# Schematic_1_v73.net
KiCad netlist of a schematic drawn in EAGLE
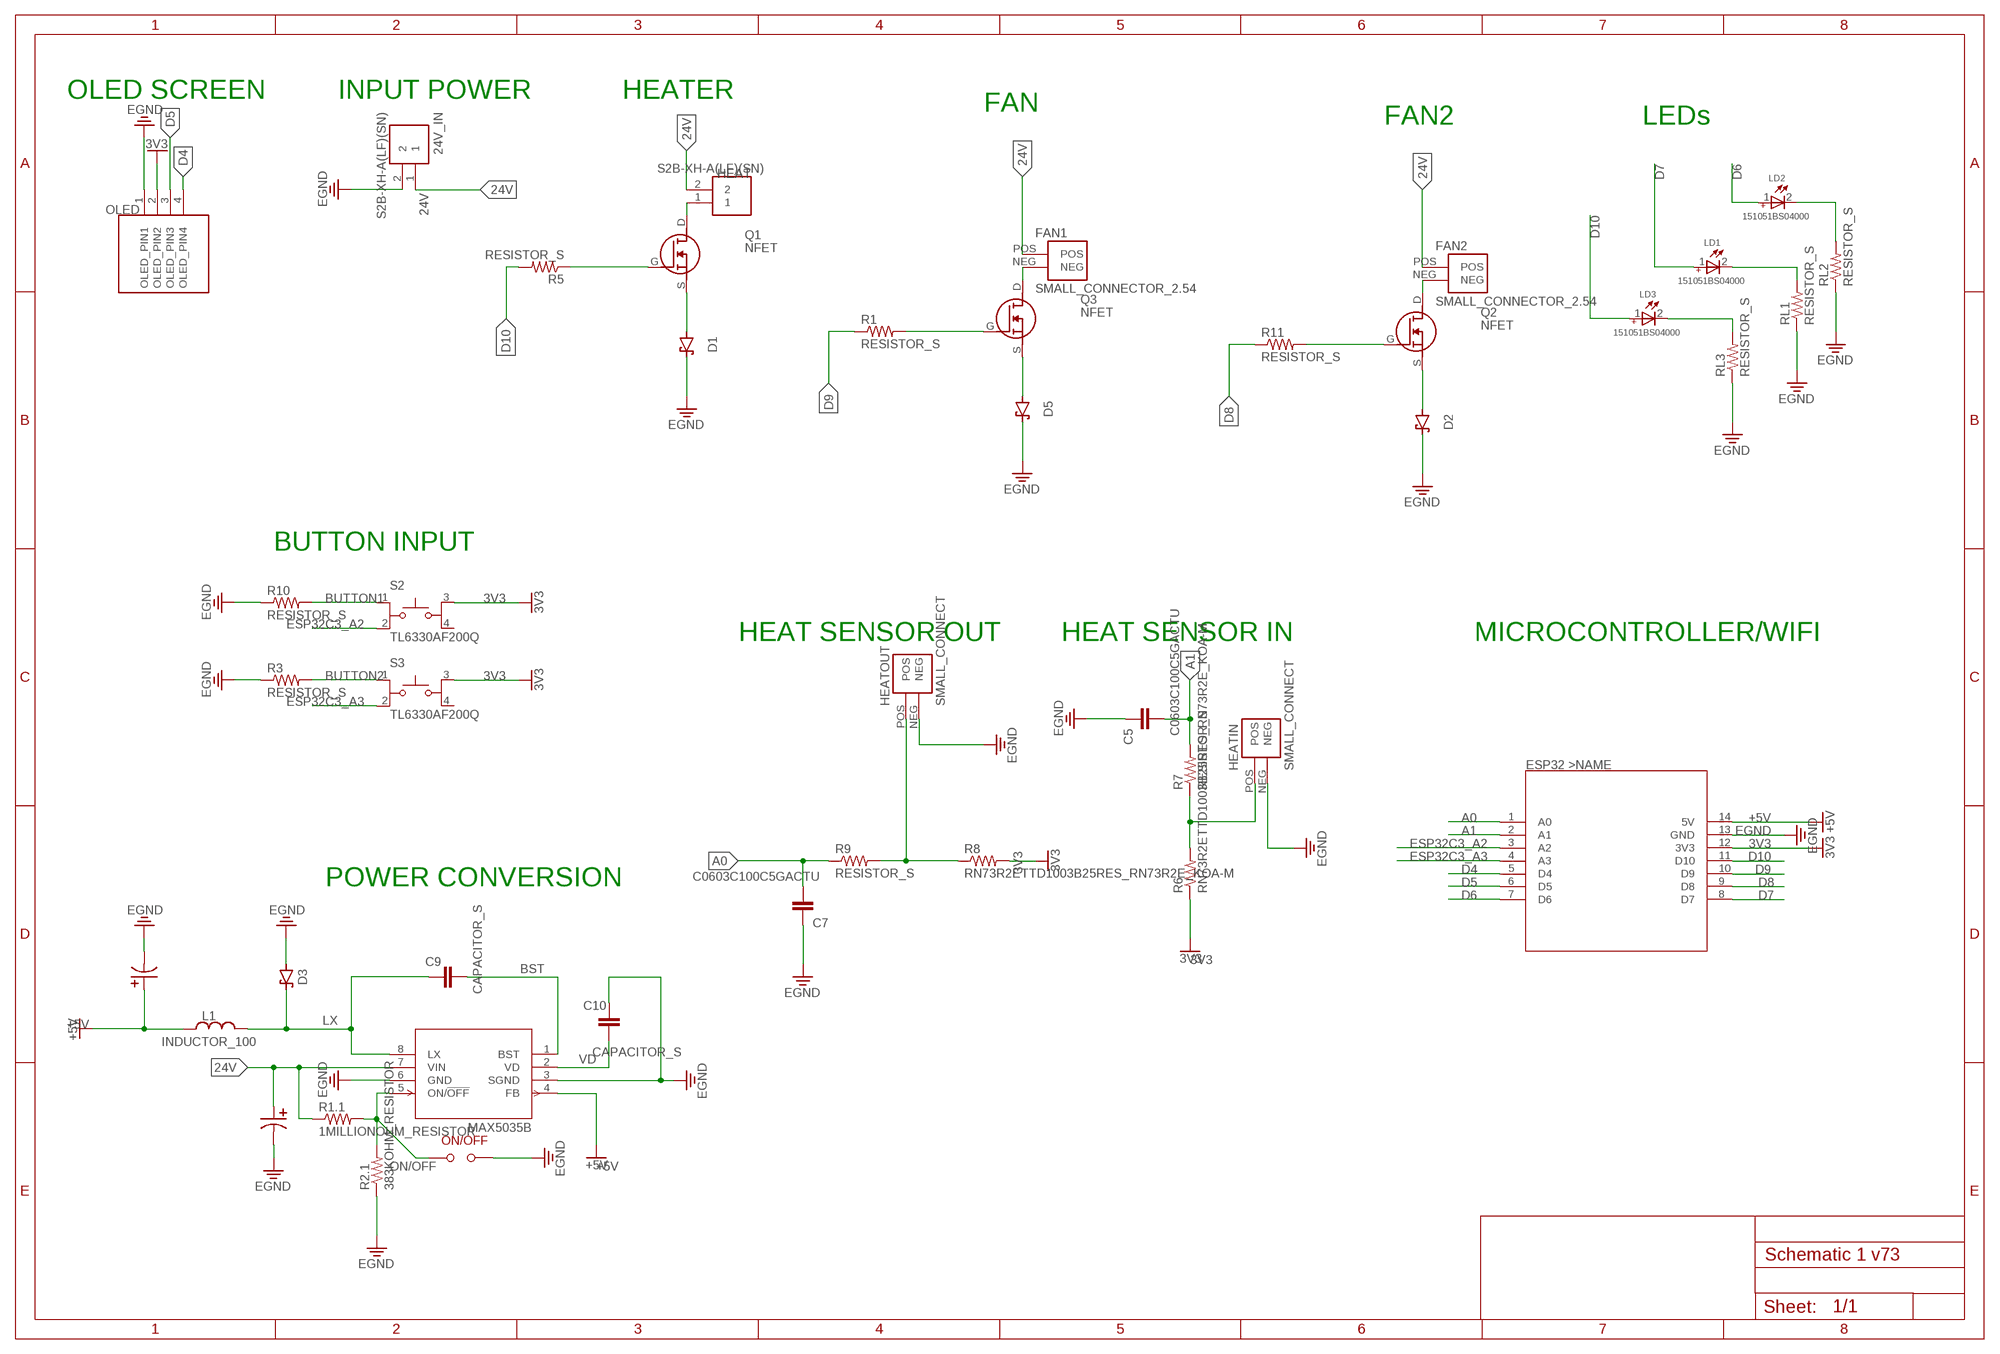
[diagram p0: schematic, sheet 1]

(export (version "E")
  (design (tool "Eeschema 10.0.6"))
  (components
    (comp (ref "24V_IN")
      (value "S2B-XH-A(LF)(SN)")
      (footprint "eagle-import:HDR-02_RA")
      (fields
        (field (name "DIGIKEY_PART_NUMBER") "455-2257-ND")
        (field (name "MANUFACTURER") "JST Sales America Inc.")
        (field (name "CREATED_BY") "PCBLayout.com")
      )
      (libsource (lib "eagle-import") (part "S2B-XH-A(LF)(SN)"))
    )
    (comp (ref "C5")
      (value "C0603C100C5GACTU")
      (footprint "eagle-import:CAP_0603")
      (fields
        (field (name "DIGIKEY_PART_NUMBER") "399-7814-2-ND")
        (field (name "MANUFACTURER") "KEMET")
        (field (name "CREATED_BY") "PCBLayout.com")
      )
      (libsource (lib "eagle-import") (part "C0603C100C5GACTU"))
    )
    (comp (ref "C7")
      (value "C0603C100C5GACTU")
      (footprint "eagle-import:CAP_0603")
      (fields
        (field (name "DIGIKEY_PART_NUMBER") "399-7814-2-ND")
        (field (name "MANUFACTURER") "KEMET")
        (field (name "CREATED_BY") "PCBLayout.com")
      )
      (libsource (lib "eagle-import") (part "C0603C100C5GACTU"))
    )
    (comp (ref "C9")
      (value "CAPACITOR_S")
      (footprint "eagle-import:CAPACITOR_M")
      (libsource (lib "eagle-import") (part "CAPACITOR_M"))
    )
    (comp (ref "C10")
      (value "CAPACITOR_S")
      (footprint "eagle-import:CAPACITOR_M")
      (libsource (lib "eagle-import") (part "CAPACITOR_M"))
    )
    (comp (ref "D1")
      (value "ES1D")
      (footprint "eagle-import:SCHOTTKY_DIODE_S")
      (libsource (lib "eagle-import") (part "SCHOTTKY_S"))
    )
    (comp (ref "D2")
      (value "ES1D")
      (footprint "eagle-import:SCHOTTKY_DIODE_S")
      (libsource (lib "eagle-import") (part "SCHOTTKY_S"))
    )
    (comp (ref "D3")
      (value "MBR0520LT1G")
      (footprint "eagle-import:PANJIT_SB52AFC~SB56AFC_SERIES_DIODE")
      (libsource (lib "eagle-import") (part "PANJIT_SB52AFC~SB56AFC_SERIES_DIODE_SCHOTTKY"))
    )
    (comp (ref "D5")
      (value "ES1D")
      (footprint "eagle-import:SCHOTTKY_DIODE_S")
      (libsource (lib "eagle-import") (part "SCHOTTKY_S"))
    )
    (comp (ref "ESP32C3")
      (value "XIAO_ESP32C3_ALT")
      (footprint "eagle-import:XIIO_ESP32C3_ALT")
      (libsource (lib "eagle-import") (part "XIAO_ESP32C3_ALT"))
    )
    (comp (ref "FAN1")
      (value "SMALL_CONNECTOR_2.54")
      (footprint "eagle-import:SMALL_CONNECT2.54")
      (libsource (lib "eagle-import") (part "SMALL_CONNECTOR_2.54"))
    )
    (comp (ref "FAN2")
      (value "SMALL_CONNECTOR_2.54")
      (footprint "eagle-import:SMALL_CONNECT2.54")
      (libsource (lib "eagle-import") (part "SMALL_CONNECTOR_2.54"))
    )
    (comp (ref "HEAT")
      (value "S2B-XH-A(LF)(SN)")
      (footprint "eagle-import:HDR-02_RA")
      (fields
        (field (name "DIGIKEY_PART_NUMBER") "455-2257-ND")
        (field (name "MANUFACTURER") "JST Sales America Inc.")
        (field (name "CREATED_BY") "PCBLayout.com")
      )
      (libsource (lib "eagle-import") (part "S2B-XH-A(LF)(SN)"))
    )
    (comp (ref "HEATIN")
      (value "SMALL_CONNECT")
      (footprint "eagle-import:SMALL_CONNECT")
      (libsource (lib "eagle-import") (part "SMALL_CONNECT"))
    )
    (comp (ref "HEATOUT")
      (value "SMALL_CONNECT")
      (footprint "eagle-import:SMALL_CONNECT")
      (libsource (lib "eagle-import") (part "SMALL_CONNECT"))
    )
    (comp (ref "L1")
      (value "INDUCTOR_100")
      (footprint "eagle-import:100UH_INDUCTOR")
      (libsource (lib "eagle-import") (part "100UH_INDUCTOR"))
    )
    (comp (ref "LD1")
      (value "151051BS04000")
      (footprint "eagle-import:WL-TMRC_5MM")
      (libsource (lib "eagle-import") (part "WL-TMRC_5MM_WITHOUTSTOPPER_151051BS04000"))
    )
    (comp (ref "LD2")
      (value "151051BS04000")
      (footprint "eagle-import:WL-TMRC_5MM")
      (libsource (lib "eagle-import") (part "WL-TMRC_5MM_WITHOUTSTOPPER_151051BS04000"))
    )
    (comp (ref "LD3")
      (value "151051BS04000")
      (footprint "eagle-import:WL-TMRC_5MM")
      (libsource (lib "eagle-import") (part "WL-TMRC_5MM_WITHOUTSTOPPER_151051BS04000"))
    )
    (comp (ref "OLED")
      (value "I2C_OLED")
      (footprint "eagle-import:I2C_OLED")
      (libsource (lib "eagle-import") (part "I2C_OLED"))
    )
    (comp (ref "ON/OFF")
      (value "SOLDER_JUMPER")
      (footprint "eagle-import:SOLDER_JUMPER")
      (libsource (lib "eagle-import") (part "SOLDER_JUMPER"))
    )
    (comp (ref "PC1")
      (value "POLORIZED_100UF")
      (footprint "eagle-import:TANTALUM_CAPACITOR_68UF")
      (libsource (lib "eagle-import") (part "TANTALUM_CAP"))
    )
    (comp (ref "PC2")
      (value "68UF_POLORIZED_CAP")
      (footprint "eagle-import:68UF_CAPAE830X1000N")
      (libsource (lib "eagle-import") (part "68UF_POLORIZED_CAP"))
    )
    (comp (ref "Q1")
      (value "NFET")
      (footprint "eagle-import:NFET")
      (libsource (lib "eagle-import") (part "NFET"))
    )
    (comp (ref "Q2")
      (value "NFET")
      (footprint "eagle-import:NFET")
      (libsource (lib "eagle-import") (part "NFET"))
    )
    (comp (ref "Q3")
      (value "NFET")
      (footprint "eagle-import:NFET")
      (libsource (lib "eagle-import") (part "NFET"))
    )
    (comp (ref "R1")
      (value "RESISTOR_S")
      (footprint "eagle-import:RESISTOR_S")
      (libsource (lib "eagle-import") (part "RESISTOR_S"))
    )
    (comp (ref "R1.1")
      (value "1MILLIONOHM_RESISTOR")
      (footprint "eagle-import:1MOHM_RESISTOR_SMD")
      (libsource (lib "eagle-import") (part "1MILLIONOHM_RESISTOR"))
    )
    (comp (ref "R2.1")
      (value "383KOHM_RESISTOR")
      (footprint "eagle-import:383KOHM_RESISTOR_0805")
      (libsource (lib "eagle-import") (part "383KOHM_RESISTOR"))
    )
    (comp (ref "R3")
      (value "RESISTOR_S")
      (footprint "eagle-import:RESISTOR_S")
      (libsource (lib "eagle-import") (part "RESISTOR_S"))
    )
    (comp (ref "R5")
      (value "RESISTOR_S")
      (footprint "eagle-import:RESISTOR_S")
      (libsource (lib "eagle-import") (part "RESISTOR_S"))
    )
    (comp (ref "R6")
      (value "RN73R2ETTD1003B25RES_RN73R2E_KOA-M")
      (footprint "eagle-import:RES_RN73R2E_KOA-M")
      (fields
        (field (name "MANUFACTURER_PART_NUMBER") "RN73R2ETTD1003B25")
        (field (name "COPYRIGHT") "Copyright (C) 2022 Ultra Librarian. All rights reserved.")
      )
      (libsource (lib "eagle-import") (part "RN73R2ETTD1003B25RES_RN73R2E_KOA-M"))
    )
    (comp (ref "R7")
      (value "RESISTOR_S")
      (footprint "eagle-import:RESISTOR_S")
      (libsource (lib "eagle-import") (part "RESISTOR_S"))
    )
    (comp (ref "R8")
      (value "RN73R2ETTD1003B25RES_RN73R2E_KOA-M")
      (footprint "eagle-import:RES_RN73R2E_KOA-M")
      (fields
        (field (name "MANUFACTURER_PART_NUMBER") "RN73R2ETTD1003B25")
        (field (name "COPYRIGHT") "Copyright (C) 2022 Ultra Librarian. All rights reserved.")
      )
      (libsource (lib "eagle-import") (part "RN73R2ETTD1003B25RES_RN73R2E_KOA-M"))
    )
    (comp (ref "R9")
      (value "RESISTOR_S")
      (footprint "eagle-import:RESISTOR_S")
      (libsource (lib "eagle-import") (part "RESISTOR_S"))
    )
    (comp (ref "R10")
      (value "RESISTOR_S")
      (footprint "eagle-import:RESISTOR_S")
      (libsource (lib "eagle-import") (part "RESISTOR_S"))
    )
    (comp (ref "R11")
      (value "RESISTOR_S")
      (footprint "eagle-import:RESISTOR_S")
      (libsource (lib "eagle-import") (part "RESISTOR_S"))
    )
    (comp (ref "RL1")
      (value "RESISTOR_S")
      (footprint "eagle-import:RESISTOR_S")
      (libsource (lib "eagle-import") (part "RESISTOR_S"))
    )
    (comp (ref "RL2")
      (value "RESISTOR_S")
      (footprint "eagle-import:RESISTOR_S")
      (libsource (lib "eagle-import") (part "RESISTOR_S"))
    )
    (comp (ref "RL3")
      (value "RESISTOR_S")
      (footprint "eagle-import:RESISTOR_S")
      (libsource (lib "eagle-import") (part "RESISTOR_S"))
    )
    (comp (ref "S2")
      (value "TL6330AF200Q")
      (footprint "eagle-import:SW_TL6330AF200Q")
      (fields (field (name "MANUFACTURER") "E-Switch"))
      (libsource (lib "eagle-import") (part "TL6330AF200Q"))
    )
    (comp (ref "S3")
      (value "TL6330AF200Q")
      (footprint "eagle-import:SW_TL6330AF200Q")
      (fields (field (name "MANUFACTURER") "E-Switch"))
      (libsource (lib "eagle-import") (part "TL6330AF200Q"))
    )
    (comp (ref "U1")
      (value "MAX5035BASA+T")
      (footprint "eagle-import:21-0041B_8_MXM-M")
      (libsource (lib "eagle-import") (part "MAX5035BASA+T"))
    )
  )
  (nets
    (net (code "1") (name "+5V") (class "Default")
      (node (ref "ESP32C3") (pin "14") (pinfunction "5V_14") (pintype "power_in"))
      (node (ref "L1") (pin "P$1") (pinfunction "1_P$1") (pintype "passive"))
      (node (ref "PC1") (pin "+") (pinfunction "POS_+") (pintype "passive"))
      (node (ref "U1") (pin "4") (pinfunction "FB_4") (pintype "output"))
    )
    (net (code "2") (name "/BST") (class "Default")
      (node (ref "C9") (pin "2") (pinfunction "2_2") (pintype "passive"))
      (node (ref "U1") (pin "1") (pinfunction "BST_1") (pintype "passive"))
    )
    (net (code "3") (name "/BUTTON1") (class "Default")
      (node (ref "R10") (pin "1") (pinfunction "P$1_1") (pintype "passive"))
      (node (ref "S2") (pin "1") (pinfunction "1_1") (pintype "passive"))
    )
    (net (code "4") (name "/BUTTON2") (class "Default")
      (node (ref "R3") (pin "1") (pinfunction "P$1_1") (pintype "passive"))
      (node (ref "S3") (pin "1") (pinfunction "1_1") (pintype "passive"))
    )
    (net (code "5") (name "/D6") (class "Default")
      (node (ref "ESP32C3") (pin "7") (pinfunction "D6_7") (pintype "bidirectional"))
      (node (ref "LD2") (pin "1") (pinfunction "+_1") (pintype "passive"))
    )
    (net (code "6") (name "/D7") (class "Default")
      (node (ref "ESP32C3") (pin "8") (pinfunction "D7_8") (pintype "bidirectional"))
      (node (ref "LD1") (pin "1") (pinfunction "+_1") (pintype "passive"))
    )
    (net (code "7") (name "/ESP32C3_A2") (class "Default")
      (node (ref "ESP32C3") (pin "3") (pinfunction "A2_3") (pintype "bidirectional"))
      (node (ref "S2") (pin "2") (pinfunction "2_2") (pintype "passive"))
    )
    (net (code "8") (name "/ESP32C3_A3") (class "Default")
      (node (ref "ESP32C3") (pin "4") (pinfunction "A3_4") (pintype "bidirectional"))
      (node (ref "S3") (pin "2") (pinfunction "2_2") (pintype "passive"))
    )
    (net (code "9") (name "/LX") (class "Default")
      (node (ref "C9") (pin "1") (pinfunction "1_1") (pintype "passive"))
      (node (ref "D3") (pin "NEG") (pinfunction "NEG_NEG") (pintype "passive"))
      (node (ref "L1") (pin "P$2") (pinfunction "2_P$2") (pintype "passive"))
      (node (ref "U1") (pin "8") (pinfunction "LX_8") (pintype "passive"))
    )
    (net (code "10") (name "/ON{slash}OFF") (class "Default")
      (node (ref "ON/OFF") (pin "P$1") (pinfunction "P$1_P$1") (pintype "passive"))
      (node (ref "R1.1") (pin "1") (pinfunction "P$1_1") (pintype "passive"))
      (node (ref "R2.1") (pin "1") (pinfunction "P$1_1") (pintype "passive"))
      (node (ref "U1") (pin "5") (pinfunction "ON/~{OFF}_5") (pintype "input"))
    )
    (net (code "11") (name "/VD") (class "Default")
      (node (ref "C10") (pin "2") (pinfunction "2_2") (pintype "passive"))
      (node (ref "U1") (pin "2") (pinfunction "VD_2") (pintype "power_in"))
    )
    (net (code "12") (name "3V3") (class "Default")
      (node (ref "ESP32C3") (pin "12") (pinfunction "3V3_12") (pintype "power_in"))
      (node (ref "OLED") (pin "2") (pinfunction "OLED_PIN2_2") (pintype "power_in"))
      (node (ref "R6") (pin "2") (pinfunction "P$2_2") (pintype "passive"))
      (node (ref "R8") (pin "1") (pinfunction "P$1_1") (pintype "passive"))
      (node (ref "S2") (pin "3") (pinfunction "3_3") (pintype "passive"))
      (node (ref "S3") (pin "3") (pinfunction "3_3") (pintype "passive"))
    )
    (net (code "13") (name "24V") (class "Default")
      (node (ref "24V_IN") (pin "1") (pinfunction "1_1") (pintype "passive"))
      (node (ref "FAN1") (pin "POS") (pinfunction "POS_POS") (pintype "passive"))
      (node (ref "FAN2") (pin "POS") (pinfunction "POS_POS") (pintype "passive"))
      (node (ref "HEAT") (pin "2") (pinfunction "2_2") (pintype "passive"))
      (node (ref "PC2") (pin "POS") (pinfunction "POS_POS") (pintype "passive"))
      (node (ref "R1.1") (pin "2") (pinfunction "P$2_2") (pintype "passive"))
      (node (ref "U1") (pin "7") (pinfunction "VIN_7") (pintype "power_in"))
    )
    (net (code "14") (name "A0") (class "Default")
      (node (ref "C7") (pin "2") (pinfunction "2_2") (pintype "passive"))
      (node (ref "ESP32C3") (pin "1") (pinfunction "A0_1") (pintype "bidirectional"))
      (node (ref "R9") (pin "2") (pinfunction "P$2_2") (pintype "passive"))
    )
    (net (code "15") (name "A1") (class "Default")
      (node (ref "C5") (pin "2") (pinfunction "2_2") (pintype "passive"))
      (node (ref "ESP32C3") (pin "2") (pinfunction "A1_2") (pintype "bidirectional"))
      (node (ref "R7") (pin "1") (pinfunction "P$1_1") (pintype "passive"))
    )
    (net (code "16") (name "D4") (class "Default")
      (node (ref "ESP32C3") (pin "5") (pinfunction "D4_5") (pintype "bidirectional"))
      (node (ref "OLED") (pin "4") (pinfunction "OLED_PIN4_4") (pintype "input"))
    )
    (net (code "17") (name "D5") (class "Default")
      (node (ref "ESP32C3") (pin "6") (pinfunction "D5_6") (pintype "bidirectional"))
      (node (ref "OLED") (pin "3") (pinfunction "OLED_PIN3_3") (pintype "input"))
    )
    (net (code "18") (name "D8") (class "Default")
      (node (ref "ESP32C3") (pin "9") (pinfunction "D8_9") (pintype "bidirectional"))
      (node (ref "R11") (pin "2") (pinfunction "P$2_2") (pintype "passive"))
    )
    (net (code "19") (name "D9") (class "Default")
      (node (ref "ESP32C3") (pin "10") (pinfunction "D9_10") (pintype "bidirectional"))
      (node (ref "R1") (pin "2") (pinfunction "P$2_2") (pintype "passive"))
    )
    (net (code "20") (name "D10") (class "Default")
      (node (ref "ESP32C3") (pin "11") (pinfunction "D10_11") (pintype "bidirectional"))
      (node (ref "LD3") (pin "1") (pinfunction "+_1") (pintype "passive"))
      (node (ref "R5") (pin "1") (pinfunction "P$1_1") (pintype "passive"))
    )
    (net (code "21") (name "EGND") (class "Default")
      (node (ref "24V_IN") (pin "2") (pinfunction "2_2") (pintype "passive"))
      (node (ref "C10") (pin "1") (pinfunction "1_1") (pintype "passive"))
      (node (ref "C5") (pin "1") (pinfunction "1_1") (pintype "passive"))
      (node (ref "C7") (pin "1") (pinfunction "1_1") (pintype "passive"))
      (node (ref "D1") (pin "NEG") (pinfunction "NEG_NEG") (pintype "passive"))
      (node (ref "D2") (pin "NEG") (pinfunction "NEG_NEG") (pintype "passive"))
      (node (ref "D3") (pin "POS") (pinfunction "POS_POS") (pintype "passive"))
      (node (ref "D5") (pin "NEG") (pinfunction "NEG_NEG") (pintype "passive"))
      (node (ref "ESP32C3") (pin "13") (pinfunction "GND_13") (pintype "power_in"))
      (node (ref "HEATIN") (pin "NEG") (pinfunction "NEG_NEG") (pintype "passive"))
      (node (ref "HEATOUT") (pin "NEG") (pinfunction "NEG_NEG") (pintype "passive"))
      (node (ref "OLED") (pin "1") (pinfunction "OLED_PIN1_1") (pintype "power_in"))
      (node (ref "ON/OFF") (pin "P$2") (pinfunction "P$2_P$2") (pintype "passive"))
      (node (ref "PC1") (pin "-") (pinfunction "NEG_-") (pintype "passive"))
      (node (ref "PC2") (pin "NEG") (pinfunction "NEG_NEG") (pintype "passive"))
      (node (ref "R10") (pin "2") (pinfunction "P$2_2") (pintype "passive"))
      (node (ref "R2.1") (pin "2") (pinfunction "P$2_2") (pintype "passive"))
      (node (ref "R3") (pin "2") (pinfunction "P$2_2") (pintype "passive"))
      (node (ref "RL1") (pin "2") (pinfunction "P$2_2") (pintype "passive"))
      (node (ref "RL2") (pin "2") (pinfunction "P$2_2") (pintype "passive"))
      (node (ref "RL3") (pin "2") (pinfunction "P$2_2") (pintype "passive"))
      (node (ref "U1") (pin "3") (pinfunction "SGND_3") (pintype "power_in"))
      (node (ref "U1") (pin "6") (pinfunction "GND_6") (pintype "power_in"))
    )
    (net (code "22") (name "Net-(D1-PadPOS)") (class "Default")
      (node (ref "D1") (pin "POS") (pinfunction "POS_POS") (pintype "passive"))
      (node (ref "Q1") (pin "S") (pinfunction "S_S") (pintype "bidirectional"))
    )
    (net (code "23") (name "Net-(D2-PadPOS)") (class "Default")
      (node (ref "D2") (pin "POS") (pinfunction "POS_POS") (pintype "passive"))
      (node (ref "Q2") (pin "S") (pinfunction "S_S") (pintype "bidirectional"))
    )
    (net (code "24") (name "Net-(D5-PadPOS)") (class "Default")
      (node (ref "D5") (pin "POS") (pinfunction "POS_POS") (pintype "passive"))
      (node (ref "Q3") (pin "S") (pinfunction "S_S") (pintype "bidirectional"))
    )
    (net (code "25") (name "Net-(FAN1-PadNEG)") (class "Default")
      (node (ref "FAN1") (pin "NEG") (pinfunction "NEG_NEG") (pintype "passive"))
      (node (ref "Q3") (pin "D") (pinfunction "D_D") (pintype "bidirectional"))
    )
    (net (code "26") (name "Net-(FAN2-PadNEG)") (class "Default")
      (node (ref "FAN2") (pin "NEG") (pinfunction "NEG_NEG") (pintype "passive"))
      (node (ref "Q2") (pin "D") (pinfunction "D_D") (pintype "bidirectional"))
    )
    (net (code "27") (name "Net-(HEAT-Pad1)") (class "Default")
      (node (ref "HEAT") (pin "1") (pinfunction "1_1") (pintype "passive"))
      (node (ref "Q1") (pin "D") (pinfunction "D_D") (pintype "bidirectional"))
    )
    (net (code "28") (name "Net-(LD1--)") (class "Default")
      (node (ref "LD1") (pin "2") (pinfunction "-_2") (pintype "passive"))
      (node (ref "RL1") (pin "1") (pinfunction "P$1_1") (pintype "passive"))
    )
    (net (code "29") (name "Net-(LD2--)") (class "Default")
      (node (ref "LD2") (pin "2") (pinfunction "-_2") (pintype "passive"))
      (node (ref "RL2") (pin "1") (pinfunction "P$1_1") (pintype "passive"))
    )
    (net (code "30") (name "Net-(LD3--)") (class "Default")
      (node (ref "LD3") (pin "2") (pinfunction "-_2") (pintype "passive"))
      (node (ref "RL3") (pin "1") (pinfunction "P$1_1") (pintype "passive"))
    )
    (net (code "31") (name "Net-(R1-P$1)") (class "Default")
      (node (ref "Q3") (pin "G") (pinfunction "G_G") (pintype "bidirectional"))
      (node (ref "R1") (pin "1") (pinfunction "P$1_1") (pintype "passive"))
    )
    (net (code "32") (name "Net-(R5-P$2)") (class "Default")
      (node (ref "Q1") (pin "G") (pinfunction "G_G") (pintype "bidirectional"))
      (node (ref "R5") (pin "2") (pinfunction "P$2_2") (pintype "passive"))
    )
    (net (code "33") (name "Net-(R6-P$1)") (class "Default")
      (node (ref "HEATIN") (pin "POS") (pinfunction "POS_POS") (pintype "passive"))
      (node (ref "R6") (pin "1") (pinfunction "P$1_1") (pintype "passive"))
      (node (ref "R7") (pin "2") (pinfunction "P$2_2") (pintype "passive"))
    )
    (net (code "34") (name "Net-(R8-P$2)") (class "Default")
      (node (ref "HEATOUT") (pin "POS") (pinfunction "POS_POS") (pintype "passive"))
      (node (ref "R8") (pin "2") (pinfunction "P$2_2") (pintype "passive"))
      (node (ref "R9") (pin "1") (pinfunction "P$1_1") (pintype "passive"))
    )
    (net (code "35") (name "Net-(R11-P$1)") (class "Default")
      (node (ref "Q2") (pin "G") (pinfunction "G_G") (pintype "bidirectional"))
      (node (ref "R11") (pin "1") (pinfunction "P$1_1") (pintype "passive"))
    )
    (net (code "36") (name "unconnected-(S2-Pad4)") (class "Default")
      (node (ref "S2") (pin "4") (pinfunction "4_4") (pintype "passive"))
    )
    (net (code "37") (name "unconnected-(S3-Pad4)") (class "Default")
      (node (ref "S3") (pin "4") (pinfunction "4_4") (pintype "passive"))
    )
  )
)
